# NEO-M8T_GNSS_FeatherWing.net
KiCad netlist of a schematic drawn in EAGLE
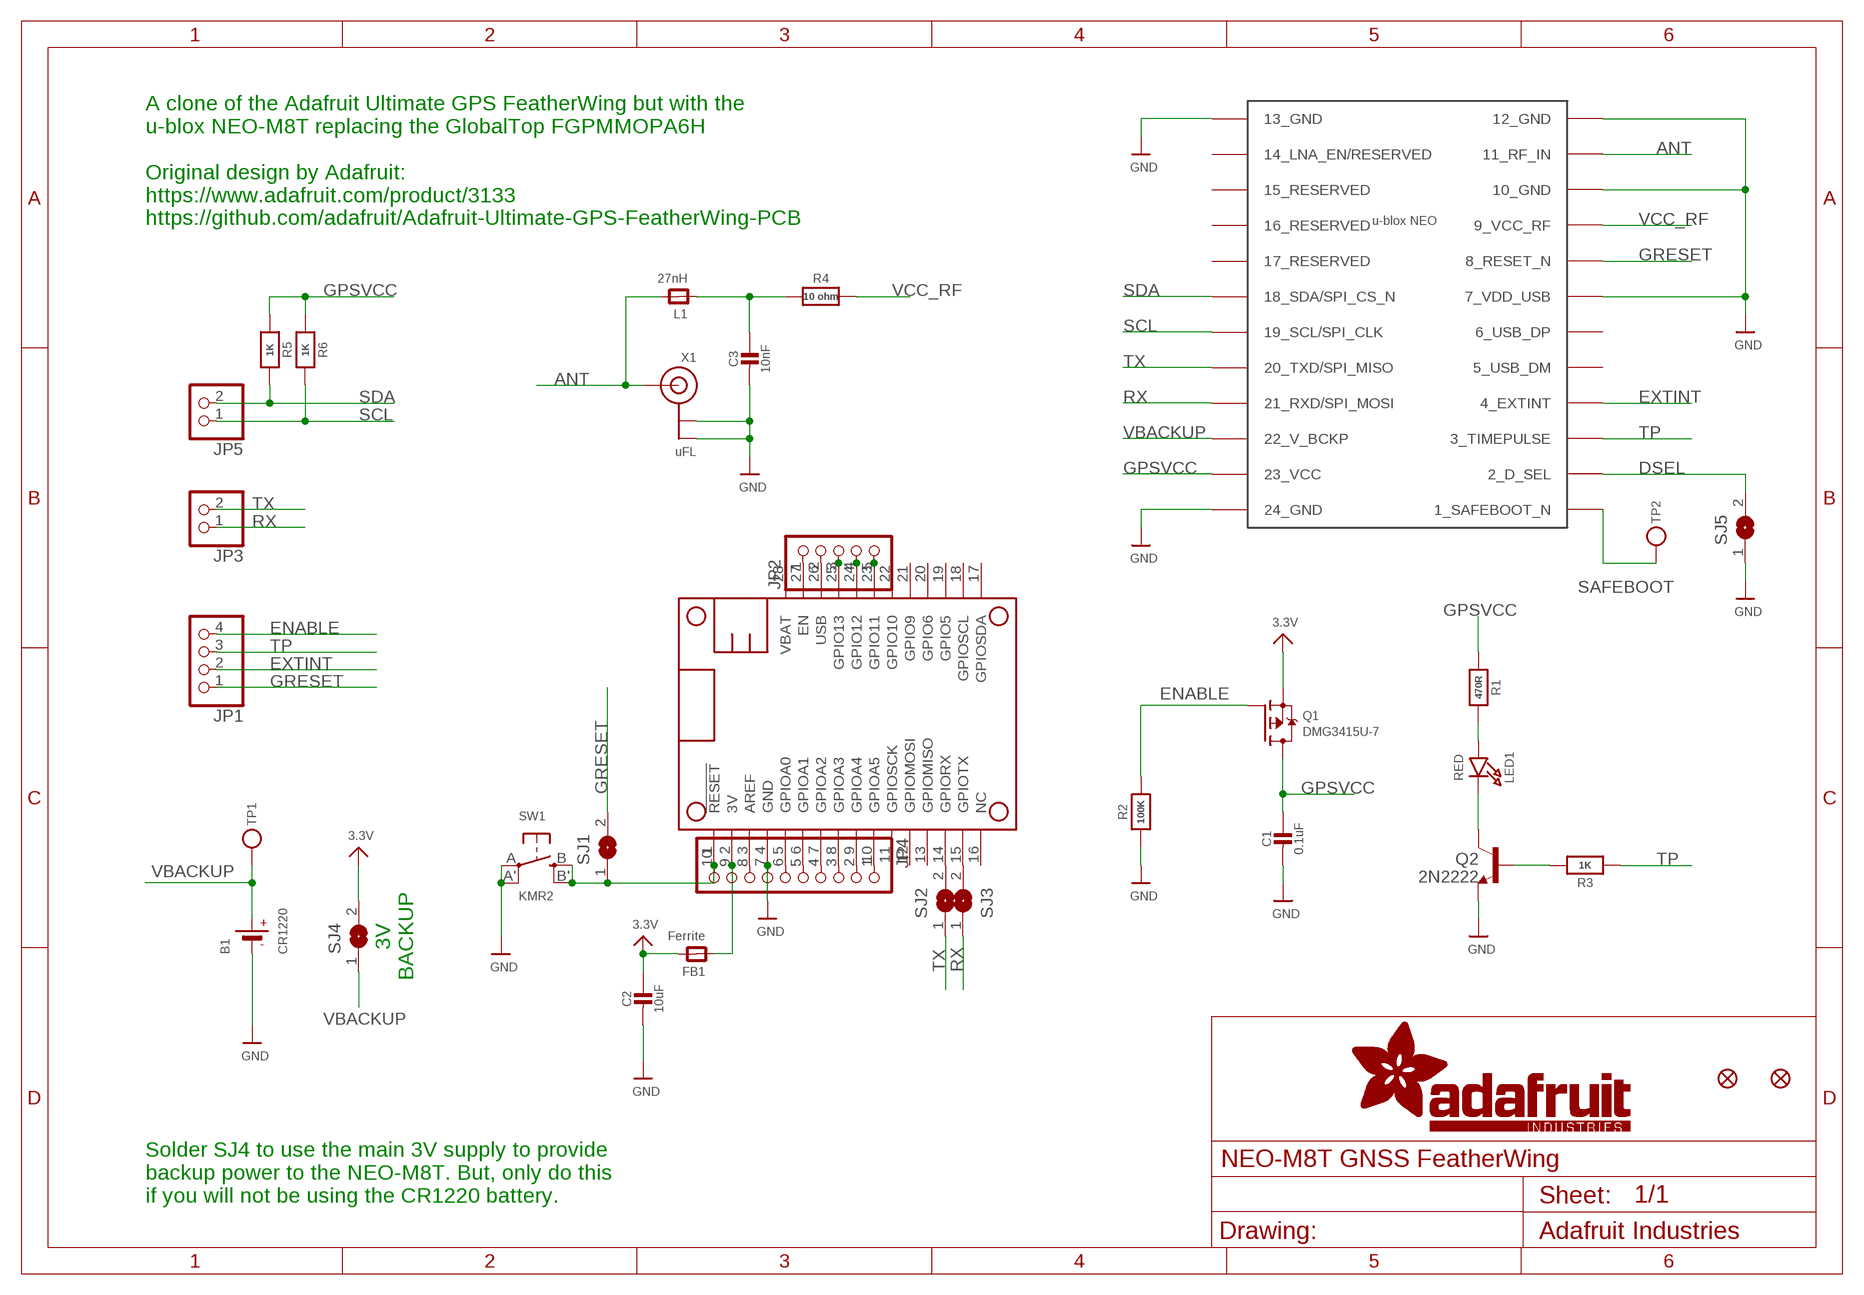
[diagram p0: schematic, sheet 1]

(export (version "E")
  (design (tool "Eeschema 10.0.6"))
  (components
    (comp (ref "B1")
      (value "CR1220")
      (footprint "eagle-import:CR1220-2")
      (libsource (lib "eagle-import") (part "BATTERYCR1220_2"))
    )
    (comp (ref "C1")
      (value "0.1uF")
      (footprint "eagle-import:0805-NO")
      (libsource (lib "eagle-import") (part "CAP_CERAMIC0805-NOOUTLINE"))
    )
    (comp (ref "C2")
      (value "10uF")
      (footprint "eagle-import:0805-NO")
      (libsource (lib "eagle-import") (part "CAP_CERAMIC0805-NOOUTLINE"))
    )
    (comp (ref "C3")
      (value "10nF")
      (footprint "eagle-import:0805-NO")
      (libsource (lib "eagle-import") (part "CAP_CERAMIC0805-NOOUTLINE"))
    )
    (comp (ref "FB1")
      (value "Ferrite")
      (footprint "eagle-import:0805-NO")
      (libsource (lib "eagle-import") (part "FERRITE-0805NO"))
    )
    (comp (ref "FID1")
      (value "FIDUCIAL\"\"")
      (footprint "eagle-import:FIDUCIAL_1MM")
      (libsource (lib "eagle-import") (part "FIDUCIAL{dblquote}{dblquote}"))
    )
    (comp (ref "FID2")
      (value "FIDUCIAL\"\"")
      (footprint "eagle-import:FIDUCIAL_1MM")
      (libsource (lib "eagle-import") (part "FIDUCIAL{dblquote}{dblquote}"))
    )
    (comp (ref "JP1")
      (value "HEADER-1X4ROUND")
      (footprint "eagle-import:1X04_ROUND")
      (libsource (lib "eagle-import") (part "HEADER-1X4ROUND"))
    )
    (comp (ref "JP2")
      (value "HEADER-1X570MIL")
      (footprint "eagle-import:1X05_ROUND_70")
      (libsource (lib "eagle-import") (part "HEADER-1X570MIL"))
    )
    (comp (ref "JP3")
      (value "HEADER-1X2ROUND")
      (footprint "eagle-import:1X02_ROUND")
      (libsource (lib "eagle-import") (part "HEADER-1X2ROUND"))
    )
    (comp (ref "JP4")
      (value "HEADER-1X10ROUND")
      (footprint "eagle-import:1X10_ROUND")
      (libsource (lib "eagle-import") (part "HEADER-1X10ROUND"))
    )
    (comp (ref "JP5")
      (value "HEADER-1X2ROUND")
      (footprint "eagle-import:1X02_ROUND")
      (libsource (lib "eagle-import") (part "HEADER-1X2ROUND"))
    )
    (comp (ref "L1")
      (value "27nH")
      (footprint "eagle-import:0805-NO")
      (libsource (lib "eagle-import") (part "FERRITE-0805NO"))
    )
    (comp (ref "LED1")
      (value "RED")
      (footprint "eagle-import:CHIPLED_0805_NOOUTLINE")
      (libsource (lib "eagle-import") (part "LED0805_NOOUTLINE"))
    )
    (comp (ref "MS1")
      (value "FEATHERWING")
      (footprint "eagle-import:FEATHERWING")
      (libsource (lib "eagle-import") (part "FEATHERWING"))
    )
    (comp (ref "Q1")
      (value "DMG3415U-7")
      (footprint "eagle-import:SOT23-WIDE")
      (libsource (lib "eagle-import") (part "MOSFET-PWIDE"))
    )
    (comp (ref "Q2")
      (value "2N2222")
      (footprint "eagle-import:SOT23-BEC")
      (libsource (lib "eagle-import") (part "-NPN-SOT23-BECMMBT2222ALT1"))
    )
    (comp (ref "R1")
      (value "470R")
      (footprint "eagle-import:0603-NO")
      (libsource (lib "eagle-import") (part "RESISTOR_0603_NOOUT"))
    )
    (comp (ref "R2")
      (value "100K")
      (footprint "eagle-import:0805-NO")
      (libsource (lib "eagle-import") (part "RESISTOR0805_NOOUTLINE"))
    )
    (comp (ref "R3")
      (value "1K")
      (footprint "eagle-import:0603-NO")
      (libsource (lib "eagle-import") (part "RESISTOR_0603_NOOUT"))
    )
    (comp (ref "R4")
      (value "10 ohm")
      (footprint "eagle-import:0805-NO")
      (libsource (lib "eagle-import") (part "RESISTOR0805_NOOUTLINE"))
    )
    (comp (ref "R5")
      (value "1K")
      (footprint "eagle-import:0603-NO")
      (libsource (lib "eagle-import") (part "RESISTOR_0603_NOOUT"))
    )
    (comp (ref "R6")
      (value "1K")
      (footprint "eagle-import:0603-NO")
      (libsource (lib "eagle-import") (part "RESISTOR_0603_NOOUT"))
    )
    (comp (ref "SJ1")
      (value "SOLDERJUMPER")
      (footprint "eagle-import:SOLDERJUMPER_ARROW_NOPASTE")
      (libsource (lib "eagle-import") (part "SOLDERJUMPER"))
    )
    (comp (ref "SJ2")
      (value "SOLDERJUMPERCLOSED")
      (footprint "eagle-import:SOLDERJUMPER_CLOSEDWIRE")
      (libsource (lib "eagle-import") (part "SOLDERJUMPERCLOSED"))
    )
    (comp (ref "SJ3")
      (value "SOLDERJUMPERCLOSED")
      (footprint "eagle-import:SOLDERJUMPER_CLOSEDWIRE")
      (libsource (lib "eagle-import") (part "SOLDERJUMPERCLOSED"))
    )
    (comp (ref "SJ4")
      (value "SOLDERJUMPER")
      (footprint "eagle-import:SOLDERJUMPER_ARROW_NOPASTE")
      (libsource (lib "eagle-import") (part "SOLDERJUMPER"))
    )
    (comp (ref "SJ5")
      (value "SOLDERJUMPER")
      (footprint "eagle-import:SOLDERJUMPER_ARROW_NOPASTE")
      (libsource (lib "eagle-import") (part "SOLDERJUMPER"))
    )
    (comp (ref "SW1")
      (value "KMR2")
      (footprint "eagle-import:BTN_KMR2_4.6X2.8")
      (libsource (lib "eagle-import") (part "SWITCH_TACT_SMT4.6X2.8"))
    )
    (comp (ref "TP1")
      (value "TESTPOINTROUND1.5MM")
      (footprint "eagle-import:TESTPOINT_ROUND_1.5MM")
      (libsource (lib "eagle-import") (part "TESTPOINTROUND1.5MM"))
    )
    (comp (ref "TP2")
      (value "TESTPOINTROUND1.5MM")
      (footprint "eagle-import:TESTPOINT_ROUND_1.5MM")
      (libsource (lib "eagle-import") (part "TESTPOINTROUND1.5MM"))
    )
    (comp (ref "U1")
      (value "NEO-M8")
      (footprint "eagle-import:NEO-M8")
      (libsource (lib "eagle-import") (part "NEO-M8"))
    )
    (comp (ref "X1")
      (value "uFL")
      (footprint "eagle-import:U.FL")
      (libsource (lib "eagle-import") (part "ANTENNA_U.FL"))
    )
  )
  (nets
    (net (code "1") (name "/ANT") (class "Default")
      (node (ref "L1") (pin "2") (pinfunction "P$2_2") (pintype "passive"))
      (node (ref "U1") (pin "11") (pinfunction "11_RF_IN_11") (pintype "bidirectional"))
      (node (ref "X1") (pin "3") (pinfunction "SIGNAL_3") (pintype "passive"))
    )
    (net (code "2") (name "/DSEL") (class "Default")
      (node (ref "SJ5") (pin "2") (pinfunction "2_2") (pintype "passive"))
      (node (ref "U1") (pin "2") (pinfunction "2_D_SEL_2") (pintype "bidirectional"))
    )
    (net (code "3") (name "/ENABLE") (class "Default")
      (node (ref "JP1") (pin "4") (pinfunction "4_4") (pintype "passive"))
      (node (ref "Q1") (pin "1") (pinfunction "G_1") (pintype "passive"))
      (node (ref "R2") (pin "2") (pinfunction "2_2") (pintype "passive"))
    )
    (net (code "4") (name "/EXTINT") (class "Default")
      (node (ref "JP1") (pin "2") (pinfunction "2_2") (pintype "passive"))
      (node (ref "U1") (pin "4") (pinfunction "4_EXTINT_4") (pintype "bidirectional"))
    )
    (net (code "5") (name "/GPSVCC") (class "Default")
      (node (ref "C1") (pin "1") (pinfunction "1_1") (pintype "passive"))
      (node (ref "Q1") (pin "3") (pinfunction "D_3") (pintype "passive"))
      (node (ref "R1") (pin "1") (pinfunction "1_1") (pintype "passive"))
      (node (ref "R5") (pin "1") (pinfunction "1_1") (pintype "passive"))
      (node (ref "R6") (pin "1") (pinfunction "1_1") (pintype "passive"))
      (node (ref "U1") (pin "23") (pinfunction "23_VCC_23") (pintype "bidirectional"))
    )
    (net (code "6") (name "/GRESET") (class "Default")
      (node (ref "JP1") (pin "1") (pinfunction "1_1") (pintype "passive"))
      (node (ref "SJ1") (pin "2") (pinfunction "2_2") (pintype "passive"))
      (node (ref "U1") (pin "8") (pinfunction "8_RESET_N_8") (pintype "bidirectional"))
    )
    (net (code "7") (name "/RX") (class "Default")
      (node (ref "JP3") (pin "1") (pinfunction "1_1") (pintype "passive"))
      (node (ref "SJ3") (pin "1") (pinfunction "1_1") (pintype "passive"))
      (node (ref "U1") (pin "21") (pinfunction "21_RXD/SPI_MOSI_21") (pintype "bidirectional"))
    )
    (net (code "8") (name "/SAFEBOOT") (class "Default")
      (node (ref "TP2") (pin "P$1") (pinfunction "P$1_P$1") (pintype "bidirectional"))
      (node (ref "U1") (pin "1") (pinfunction "1_SAFEBOOT_N_1") (pintype "bidirectional"))
    )
    (net (code "9") (name "/SCL") (class "Default")
      (node (ref "JP5") (pin "1") (pinfunction "1_1") (pintype "passive"))
      (node (ref "R6") (pin "2") (pinfunction "2_2") (pintype "passive"))
      (node (ref "U1") (pin "19") (pinfunction "19_SCL/SPI_CLK_19") (pintype "bidirectional"))
    )
    (net (code "10") (name "/SDA") (class "Default")
      (node (ref "JP5") (pin "2") (pinfunction "2_2") (pintype "passive"))
      (node (ref "R5") (pin "2") (pinfunction "2_2") (pintype "passive"))
      (node (ref "U1") (pin "18") (pinfunction "18_SDA/SPI_CS_N_18") (pintype "bidirectional"))
    )
    (net (code "11") (name "/TP") (class "Default")
      (node (ref "JP1") (pin "3") (pinfunction "3_3") (pintype "passive"))
      (node (ref "R3") (pin "1") (pinfunction "1_1") (pintype "passive"))
      (node (ref "U1") (pin "3") (pinfunction "3_TIMEPULSE_3") (pintype "bidirectional"))
    )
    (net (code "12") (name "/TX") (class "Default")
      (node (ref "JP3") (pin "2") (pinfunction "2_2") (pintype "passive"))
      (node (ref "SJ2") (pin "1") (pinfunction "1_1") (pintype "passive"))
      (node (ref "U1") (pin "20") (pinfunction "20_TXD/SPI_MISO_20") (pintype "bidirectional"))
    )
    (net (code "13") (name "/VBACKUP") (class "Default")
      (node (ref "B1") (pin "+") (pinfunction "+_+") (pintype "passive"))
      (node (ref "SJ4") (pin "1") (pinfunction "1_1") (pintype "passive"))
      (node (ref "TP1") (pin "P$1") (pinfunction "P$1_P$1") (pintype "bidirectional"))
      (node (ref "U1") (pin "22") (pinfunction "22_V_BCKP_22") (pintype "bidirectional"))
    )
    (net (code "14") (name "/VBAT") (class "Default")
      (node (ref "MS1") (pin "28") (pinfunction "VBAT_28") (pintype "power_in"))
    )
    (net (code "15") (name "/VCC_RF") (class "Default")
      (node (ref "R4") (pin "2") (pinfunction "2_2") (pintype "passive"))
      (node (ref "U1") (pin "9") (pinfunction "9_VCC_RF_9") (pintype "bidirectional"))
    )
    (net (code "16") (name "3.3V") (class "Default")
      (node (ref "C2") (pin "1") (pinfunction "1_1") (pintype "passive"))
      (node (ref "FB1") (pin "2") (pinfunction "P$2_2") (pintype "passive"))
      (node (ref "Q1") (pin "2") (pinfunction "S_2") (pintype "passive"))
      (node (ref "SJ4") (pin "2") (pinfunction "2_2") (pintype "passive"))
    )
    (net (code "17") (name "GND") (class "Default")
      (node (ref "B1") (pin "-") (pinfunction "-_-") (pintype "passive"))
      (node (ref "C1") (pin "2") (pinfunction "2_2") (pintype "passive"))
      (node (ref "C2") (pin "2") (pinfunction "2_2") (pintype "passive"))
      (node (ref "C3") (pin "2") (pinfunction "2_2") (pintype "passive"))
      (node (ref "JP4") (pin "7") (pinfunction "7_7") (pintype "passive"))
      (node (ref "MS1") (pin "4") (pinfunction "GND_4") (pintype "power_in"))
      (node (ref "Q2") (pin "E") (pinfunction "E_E") (pintype "passive"))
      (node (ref "R2") (pin "1") (pinfunction "1_1") (pintype "passive"))
      (node (ref "SJ5") (pin "1") (pinfunction "1_1") (pintype "passive"))
      (node (ref "SW1") (pin "A") (pinfunction "P_A") (pintype "passive"))
      (node (ref "SW1") (pin "A'") (pinfunction "P1_A'") (pintype "passive"))
      (node (ref "U1") (pin "10") (pinfunction "10_GND_10") (pintype "bidirectional"))
      (node (ref "U1") (pin "12") (pinfunction "12_GND_12") (pintype "bidirectional"))
      (node (ref "U1") (pin "13") (pinfunction "13_GND_13") (pintype "bidirectional"))
      (node (ref "U1") (pin "24") (pinfunction "24_GND_24") (pintype "bidirectional"))
      (node (ref "U1") (pin "7") (pinfunction "7_VDD_USB_7") (pintype "bidirectional"))
      (node (ref "X1") (pin "1") (pinfunction "GND_1") (pintype "passive"))
      (node (ref "X1") (pin "2") (pinfunction "GND_2") (pintype "passive"))
    )
    (net (code "18") (name "Net-(FB1-P$1)") (class "Default")
      (node (ref "FB1") (pin "1") (pinfunction "P$1_1") (pintype "passive"))
      (node (ref "JP4") (pin "9") (pinfunction "9_9") (pintype "passive"))
      (node (ref "MS1") (pin "2") (pinfunction "3V_2") (pintype "power_in"))
    )
    (net (code "19") (name "Net-(L1-P$1)") (class "Default")
      (node (ref "C3") (pin "1") (pinfunction "1_1") (pintype "passive"))
      (node (ref "L1") (pin "1") (pinfunction "P$1_1") (pintype "passive"))
      (node (ref "R4") (pin "1") (pinfunction "1_1") (pintype "passive"))
    )
    (net (code "20") (name "Net-(LED1-PadA)") (class "Default")
      (node (ref "LED1") (pin "A") (pinfunction "A_A") (pintype "passive"))
      (node (ref "R1") (pin "2") (pinfunction "2_2") (pintype "passive"))
    )
    (net (code "21") (name "Net-(LED1-PadC)") (class "Default")
      (node (ref "LED1") (pin "C") (pinfunction "C_C") (pintype "passive"))
      (node (ref "Q2") (pin "C") (pinfunction "C_C") (pintype "passive"))
    )
    (net (code "22") (name "Net-(MS1-AREF)") (class "Default")
      (node (ref "JP4") (pin "8") (pinfunction "8_8") (pintype "passive"))
      (node (ref "MS1") (pin "3") (pinfunction "AREF_3") (pintype "passive"))
    )
    (net (code "23") (name "Net-(MS1-EN)") (class "Default")
      (node (ref "JP2") (pin "1") (pinfunction "1_1") (pintype "passive"))
      (node (ref "MS1") (pin "27") (pinfunction "EN_27") (pintype "passive"))
    )
    (net (code "24") (name "Net-(MS1-GPIO11)") (class "Default")
      (node (ref "JP2") (pin "5") (pinfunction "5_5") (pintype "passive"))
      (node (ref "MS1") (pin "23") (pinfunction "GPIO11_23") (pintype "bidirectional"))
    )
    (net (code "25") (name "Net-(MS1-GPIO12)") (class "Default")
      (node (ref "JP2") (pin "4") (pinfunction "4_4") (pintype "passive"))
      (node (ref "MS1") (pin "24") (pinfunction "GPIO12_24") (pintype "bidirectional"))
    )
    (net (code "26") (name "Net-(MS1-GPIO13)") (class "Default")
      (node (ref "JP2") (pin "3") (pinfunction "3_3") (pintype "passive"))
      (node (ref "MS1") (pin "25") (pinfunction "GPIO13_25") (pintype "bidirectional"))
    )
    (net (code "27") (name "Net-(MS1-GPIOA0)") (class "Default")
      (node (ref "JP4") (pin "6") (pinfunction "6_6") (pintype "passive"))
      (node (ref "MS1") (pin "5") (pinfunction "GPIOA0_5") (pintype "bidirectional"))
    )
    (net (code "28") (name "Net-(MS1-GPIOA1)") (class "Default")
      (node (ref "JP4") (pin "5") (pinfunction "5_5") (pintype "passive"))
      (node (ref "MS1") (pin "6") (pinfunction "GPIOA1_6") (pintype "bidirectional"))
    )
    (net (code "29") (name "Net-(MS1-GPIOA2)") (class "Default")
      (node (ref "JP4") (pin "4") (pinfunction "4_4") (pintype "passive"))
      (node (ref "MS1") (pin "7") (pinfunction "GPIOA2_7") (pintype "bidirectional"))
    )
    (net (code "30") (name "Net-(MS1-GPIOA3)") (class "Default")
      (node (ref "JP4") (pin "3") (pinfunction "3_3") (pintype "passive"))
      (node (ref "MS1") (pin "8") (pinfunction "GPIOA3_8") (pintype "bidirectional"))
    )
    (net (code "31") (name "Net-(MS1-GPIOA4)") (class "Default")
      (node (ref "JP4") (pin "2") (pinfunction "2_2") (pintype "passive"))
      (node (ref "MS1") (pin "9") (pinfunction "GPIOA4_9") (pintype "bidirectional"))
    )
    (net (code "32") (name "Net-(MS1-GPIOA5)") (class "Default")
      (node (ref "JP4") (pin "1") (pinfunction "1_1") (pintype "passive"))
      (node (ref "MS1") (pin "10") (pinfunction "GPIOA5_10") (pintype "bidirectional"))
    )
    (net (code "33") (name "Net-(MS1-GPIORX)") (class "Default")
      (node (ref "MS1") (pin "14") (pinfunction "GPIORX_14") (pintype "bidirectional"))
      (node (ref "SJ2") (pin "2") (pinfunction "2_2") (pintype "passive"))
    )
    (net (code "34") (name "Net-(MS1-GPIOTX)") (class "Default")
      (node (ref "MS1") (pin "15") (pinfunction "GPIOTX_15") (pintype "bidirectional"))
      (node (ref "SJ3") (pin "2") (pinfunction "2_2") (pintype "passive"))
    )
    (net (code "35") (name "Net-(MS1-USB)") (class "Default")
      (node (ref "JP2") (pin "2") (pinfunction "2_2") (pintype "passive"))
      (node (ref "MS1") (pin "26") (pinfunction "USB_26") (pintype "power_in"))
    )
    (net (code "36") (name "Net-(MS1-~{RESET})") (class "Default")
      (node (ref "JP4") (pin "10") (pinfunction "10_10") (pintype "passive"))
      (node (ref "MS1") (pin "1") (pinfunction "~{RESET}_1") (pintype "input"))
      (node (ref "SJ1") (pin "1") (pinfunction "1_1") (pintype "passive"))
      (node (ref "SW1") (pin "B") (pinfunction "S_B") (pintype "passive"))
      (node (ref "SW1") (pin "B'") (pinfunction "S1_B'") (pintype "passive"))
    )
    (net (code "37") (name "Net-(Q2-PadB)") (class "Default")
      (node (ref "Q2") (pin "B") (pinfunction "B_B") (pintype "passive"))
      (node (ref "R3") (pin "2") (pinfunction "2_2") (pintype "passive"))
    )
    (net (code "38") (name "unconnected-(MS1-GPIO5-Pad19)") (class "Default")
      (node (ref "MS1") (pin "19") (pinfunction "GPIO5_19") (pintype "bidirectional"))
    )
    (net (code "39") (name "unconnected-(MS1-GPIO6-Pad20)") (class "Default")
      (node (ref "MS1") (pin "20") (pinfunction "GPIO6_20") (pintype "bidirectional"))
    )
    (net (code "40") (name "unconnected-(MS1-GPIO9-Pad21)") (class "Default")
      (node (ref "MS1") (pin "21") (pinfunction "GPIO9_21") (pintype "bidirectional"))
    )
    (net (code "41") (name "unconnected-(MS1-GPIO10-Pad22)") (class "Default")
      (node (ref "MS1") (pin "22") (pinfunction "GPIO10_22") (pintype "bidirectional"))
    )
    (net (code "42") (name "unconnected-(MS1-GPIOMISO-Pad13)") (class "Default")
      (node (ref "MS1") (pin "13") (pinfunction "GPIOMISO_13") (pintype "bidirectional"))
    )
    (net (code "43") (name "unconnected-(MS1-GPIOMOSI-Pad12)") (class "Default")
      (node (ref "MS1") (pin "12") (pinfunction "GPIOMOSI_12") (pintype "bidirectional"))
    )
    (net (code "44") (name "unconnected-(MS1-GPIOSCK-Pad11)") (class "Default")
      (node (ref "MS1") (pin "11") (pinfunction "GPIOSCK_11") (pintype "bidirectional"))
    )
    (net (code "45") (name "unconnected-(MS1-GPIOSCL-Pad18)") (class "Default")
      (node (ref "MS1") (pin "18") (pinfunction "GPIOSCL_18") (pintype "bidirectional"))
    )
    (net (code "46") (name "unconnected-(MS1-GPIOSDA-Pad17)") (class "Default")
      (node (ref "MS1") (pin "17") (pinfunction "GPIOSDA_17") (pintype "bidirectional"))
    )
    (net (code "47") (name "unconnected-(MS1-NC-Pad16)") (class "Default")
      (node (ref "MS1") (pin "16") (pinfunction "NC_16") (pintype "passive"))
    )
    (net (code "48") (name "unconnected-(U1-5_USB_DM-Pad5)") (class "Default")
      (node (ref "U1") (pin "5") (pinfunction "5_USB_DM_5") (pintype "bidirectional"))
    )
    (net (code "49") (name "unconnected-(U1-6_USB_DP-Pad6)") (class "Default")
      (node (ref "U1") (pin "6") (pinfunction "6_USB_DP_6") (pintype "bidirectional"))
    )
    (net (code "50") (name "unconnected-(U1-14_LNA_EN{slash}RESERVED-Pad14)") (class "Default")
      (node (ref "U1") (pin "14") (pinfunction "14_LNA_EN/RESERVED_14") (pintype "bidirectional"))
    )
    (net (code "51") (name "unconnected-(U1-15_RESERVED-Pad15)") (class "Default")
      (node (ref "U1") (pin "15") (pinfunction "15_RESERVED_15") (pintype "bidirectional"))
    )
    (net (code "52") (name "unconnected-(U1-16_RESERVED-Pad16)") (class "Default")
      (node (ref "U1") (pin "16") (pinfunction "16_RESERVED_16") (pintype "bidirectional"))
    )
    (net (code "53") (name "unconnected-(U1-17_RESERVED-Pad17)") (class "Default")
      (node (ref "U1") (pin "17") (pinfunction "17_RESERVED_17") (pintype "bidirectional"))
    )
  )
)
